# H_bridge_core_design.net
KiCad netlist of a schematic drawn in EasyEDA
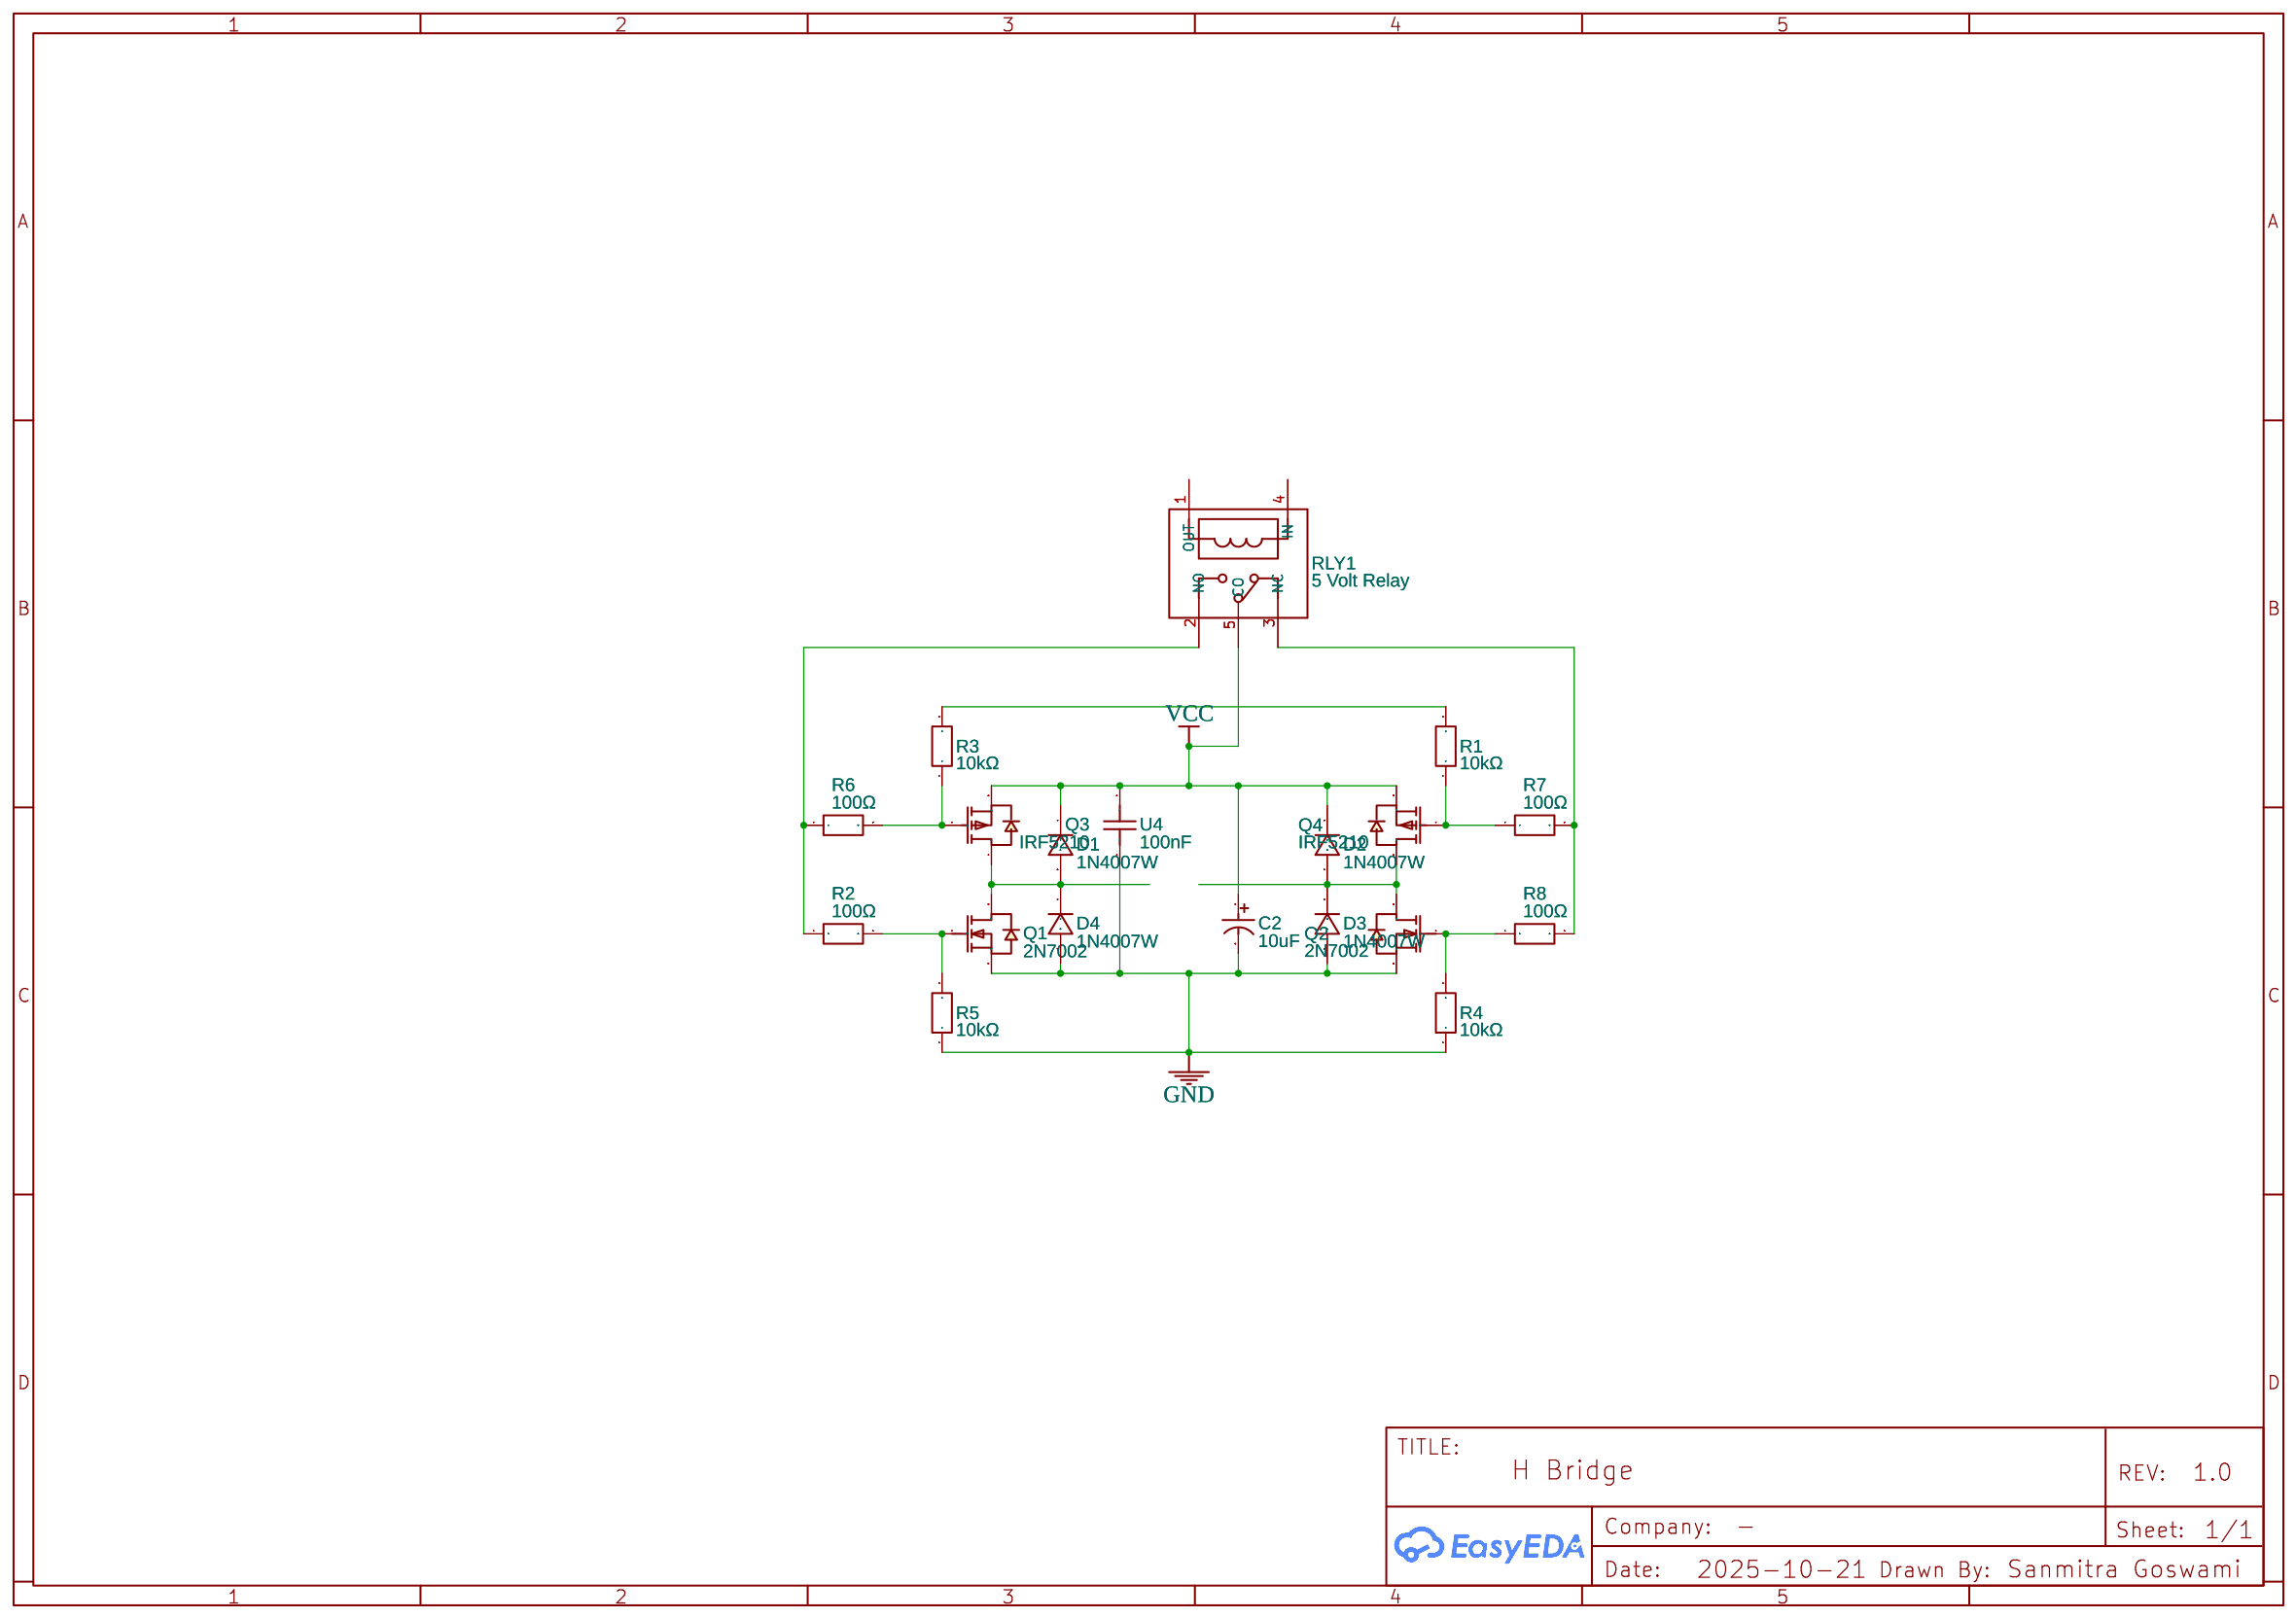
[diagram p0: schematic sheet]

(export (version "E")
  (design (tool "Eeschema 10.0.6"))
  (components
    (comp (ref "C2")
      (value "10uF")
      (fields
        (field (name "Manufacturer Part") "KS106M050C07RR0VH2FP0")
        (field (name "Manufacturer") "Chengx(承兴)")
      )
      (libsource (lib "") (part "electrolytic capacitor10UF50V"))
    )
    (comp (ref "D1")
      (value "1N4007W")
      (fields (field (name "Manufacturer") "BLUE ROCKET"))
      (libsource (lib "") (part "1N4007W"))
    )
    (comp (ref "D2")
      (value "1N4007W")
      (fields (field (name "Manufacturer") "BLUE ROCKET"))
      (libsource (lib "") (part "1N4007W"))
    )
    (comp (ref "D3")
      (value "1N4007W")
      (fields (field (name "Manufacturer") "BLUE ROCKET"))
      (libsource (lib "") (part "1N4007W"))
    )
    (comp (ref "D4")
      (value "1N4007W")
      (fields (field (name "Manufacturer") "BLUE ROCKET"))
      (libsource (lib "") (part "1N4007W"))
    )
    (comp (ref "Q1")
      (value "2N7002")
      (fields (field (name "Manufacturer Part") "2N7002,215") (field (name "Manufacturer") "Nexperia"))
      (libsource (lib "") (part "2N7002_1"))
    )
    (comp (ref "Q2")
      (value "2N7002")
      (fields (field (name "Manufacturer Part") "2N7002,215") (field (name "Manufacturer") "Nexperia"))
      (libsource (lib "") (part "2N7002"))
    )
    (comp (ref "Q3")
      (value "IRF5210")
      (fields (field (name "Manufacturer Part") "IRF5210STRLPBF") (field (name "Manufacturer") "IR"))
      (libsource (lib "") (part "IRF5210_1"))
    )
    (comp (ref "Q4")
      (value "IRF5210")
      (fields (field (name "Manufacturer Part") "IRF5210STRLPBF") (field (name "Manufacturer") "IR"))
      (libsource (lib "") (part "IRF5210"))
    )
    (comp (ref "R1")
      (value "10kΩ")
      (fields (field (name "Manufacturer Part") "TD03H1002BT") (field (name "Manufacturer") "FH(风华)"))
      (libsource (lib "") (part "TD03H1002BT"))
    )
    (comp (ref "R2")
      (value "100Ω")
      (fields (field (name "Manufacturer Part") "0603 ±5% 100Ω") (field (name "Manufacturer") "VO(翔胜)"))
      (libsource (lib "") (part "0603 ±5% 100Ω"))
    )
    (comp (ref "R3")
      (value "10kΩ")
      (fields (field (name "Manufacturer Part") "TD03H1002BT") (field (name "Manufacturer") "FH(风华)"))
      (libsource (lib "") (part "TD03H1002BT"))
    )
    (comp (ref "R4")
      (value "10kΩ")
      (fields (field (name "Manufacturer Part") "TD03H1002BT") (field (name "Manufacturer") "FH(风华)"))
      (libsource (lib "") (part "TD03H1002BT"))
    )
    (comp (ref "R5")
      (value "10kΩ")
      (fields (field (name "Manufacturer Part") "TD03H1002BT") (field (name "Manufacturer") "FH(风华)"))
      (libsource (lib "") (part "TD03H1002BT"))
    )
    (comp (ref "R6")
      (value "100Ω")
      (fields (field (name "Manufacturer Part") "0603 ±5% 100Ω") (field (name "Manufacturer") "VO(翔胜)"))
      (libsource (lib "") (part "0603 ±5% 100Ω"))
    )
    (comp (ref "R7")
      (value "100Ω")
      (fields (field (name "Manufacturer Part") "0603 ±5% 100Ω") (field (name "Manufacturer") "VO(翔胜)"))
      (libsource (lib "") (part "0603 ±5% 100Ω"))
    )
    (comp (ref "R8")
      (value "100Ω")
      (fields (field (name "Manufacturer Part") "0603 ±5% 100Ω") (field (name "Manufacturer") "VO(翔胜)"))
      (libsource (lib "") (part "0603 ±5% 100Ω"))
    )
    (comp (ref "RLY1")
      (value "5 Volt Relay")
      (fields (field (name "Manufacturer Part") "5 Volt Relay mp") (field (name "Manufacturer") "松乐"))
      (libsource (lib "") (part "5 Volt Relay"))
    )
    (comp (ref "U4")
      (value "100nF")
      (fields (field (name "Manufacturer Part") "B32559C3104K000") (field (name "Manufacturer") "TDK"))
      (libsource (lib "") (part "B32559C3104K000"))
    )
  )
  (nets
    (net (code "1") (name "GND") (class "Default")
      (node (ref "C2") (pin "2") (pinfunction "-_2") (pintype "input"))
      (node (ref "D3") (pin "2") (pinfunction "2_2") (pintype "unspecified"))
      (node (ref "D4") (pin "2") (pinfunction "2_2") (pintype "unspecified"))
      (node (ref "Q1") (pin "2") (pinfunction "S_2") (pintype "unspecified"))
      (node (ref "Q2") (pin "2") (pinfunction "S_2") (pintype "unspecified"))
      (node (ref "R4") (pin "1") (pinfunction "1_1") (pintype "unspecified"))
      (node (ref "R5") (pin "1") (pinfunction "1_1") (pintype "unspecified"))
      (node (ref "U4") (pin "1") (pinfunction "1_1") (pintype "unspecified"))
    )
    (net (code "2") (name "Net-(Q1-D)") (class "Default")
      (node (ref "D1") (pin "2") (pinfunction "2_2") (pintype "unspecified"))
      (node (ref "D4") (pin "1") (pinfunction "1_1") (pintype "unspecified"))
      (node (ref "Q1") (pin "3") (pinfunction "D_3") (pintype "unspecified"))
      (node (ref "Q3") (pin "4") (pinfunction "D_4") (pintype "unspecified"))
    )
    (net (code "3") (name "Net-(Q1-G)") (class "Default")
      (node (ref "Q1") (pin "1") (pinfunction "G_1") (pintype "unspecified"))
      (node (ref "R2") (pin "2") (pinfunction "2_2") (pintype "unspecified"))
      (node (ref "R5") (pin "2") (pinfunction "2_2") (pintype "unspecified"))
    )
    (net (code "4") (name "Net-(Q2-D)") (class "Default")
      (node (ref "D2") (pin "2") (pinfunction "2_2") (pintype "unspecified"))
      (node (ref "D3") (pin "1") (pinfunction "1_1") (pintype "unspecified"))
      (node (ref "Q2") (pin "3") (pinfunction "D_3") (pintype "unspecified"))
      (node (ref "Q4") (pin "4") (pinfunction "D_4") (pintype "unspecified"))
    )
    (net (code "5") (name "Net-(Q2-G)") (class "Default")
      (node (ref "Q2") (pin "1") (pinfunction "G_1") (pintype "unspecified"))
      (node (ref "R4") (pin "2") (pinfunction "2_2") (pintype "unspecified"))
      (node (ref "R8") (pin "1") (pinfunction "1_1") (pintype "unspecified"))
    )
    (net (code "6") (name "Net-(Q3-G)") (class "Default")
      (node (ref "Q3") (pin "1") (pinfunction "G_1") (pintype "unspecified"))
      (node (ref "R3") (pin "1") (pinfunction "1_1") (pintype "unspecified"))
      (node (ref "R6") (pin "2") (pinfunction "2_2") (pintype "unspecified"))
    )
    (net (code "7") (name "Net-(Q4-G)") (class "Default")
      (node (ref "Q4") (pin "1") (pinfunction "G_1") (pintype "unspecified"))
      (node (ref "R1") (pin "1") (pinfunction "1_1") (pintype "unspecified"))
      (node (ref "R7") (pin "1") (pinfunction "1_1") (pintype "unspecified"))
    )
    (net (code "8") (name "Net-(R1-Pad2)") (class "Default")
      (node (ref "R1") (pin "2") (pinfunction "2_2") (pintype "unspecified"))
      (node (ref "R3") (pin "2") (pinfunction "2_2") (pintype "unspecified"))
    )
    (net (code "9") (name "Net-(RLY1-NC)") (class "Default")
      (node (ref "R7") (pin "2") (pinfunction "2_2") (pintype "unspecified"))
      (node (ref "R8") (pin "2") (pinfunction "2_2") (pintype "unspecified"))
      (node (ref "RLY1") (pin "3") (pinfunction "NC_3") (pintype "unspecified"))
    )
    (net (code "10") (name "Net-(RLY1-NO)") (class "Default")
      (node (ref "R2") (pin "1") (pinfunction "1_1") (pintype "unspecified"))
      (node (ref "R6") (pin "1") (pinfunction "1_1") (pintype "unspecified"))
      (node (ref "RLY1") (pin "2") (pinfunction "NO_2") (pintype "unspecified"))
    )
    (net (code "11") (name "VCC") (class "Default")
      (node (ref "C2") (pin "1") (pinfunction "+_1") (pintype "input"))
      (node (ref "D1") (pin "1") (pinfunction "1_1") (pintype "unspecified"))
      (node (ref "D2") (pin "1") (pinfunction "1_1") (pintype "unspecified"))
      (node (ref "Q3") (pin "3") (pinfunction "S_3") (pintype "unspecified"))
      (node (ref "Q4") (pin "3") (pinfunction "S_3") (pintype "unspecified"))
      (node (ref "RLY1") (pin "5") (pinfunction "CO_5") (pintype "unspecified"))
      (node (ref "U4") (pin "2") (pinfunction "2_2") (pintype "unspecified"))
    )
    (net (code "12") (name "unconnected-(RLY1-IN-Pad4)") (class "Default")
      (node (ref "RLY1") (pin "4") (pinfunction "IN_4") (pintype "unspecified"))
    )
    (net (code "13") (name "unconnected-(RLY1-OUT-Pad1)") (class "Default")
      (node (ref "RLY1") (pin "1") (pinfunction "OUT_1") (pintype "unspecified"))
    )
  )
)
